# REX_9628_Extern_Kernel_8.net
KiCad netlist of a schematic drawn in Altium Designer
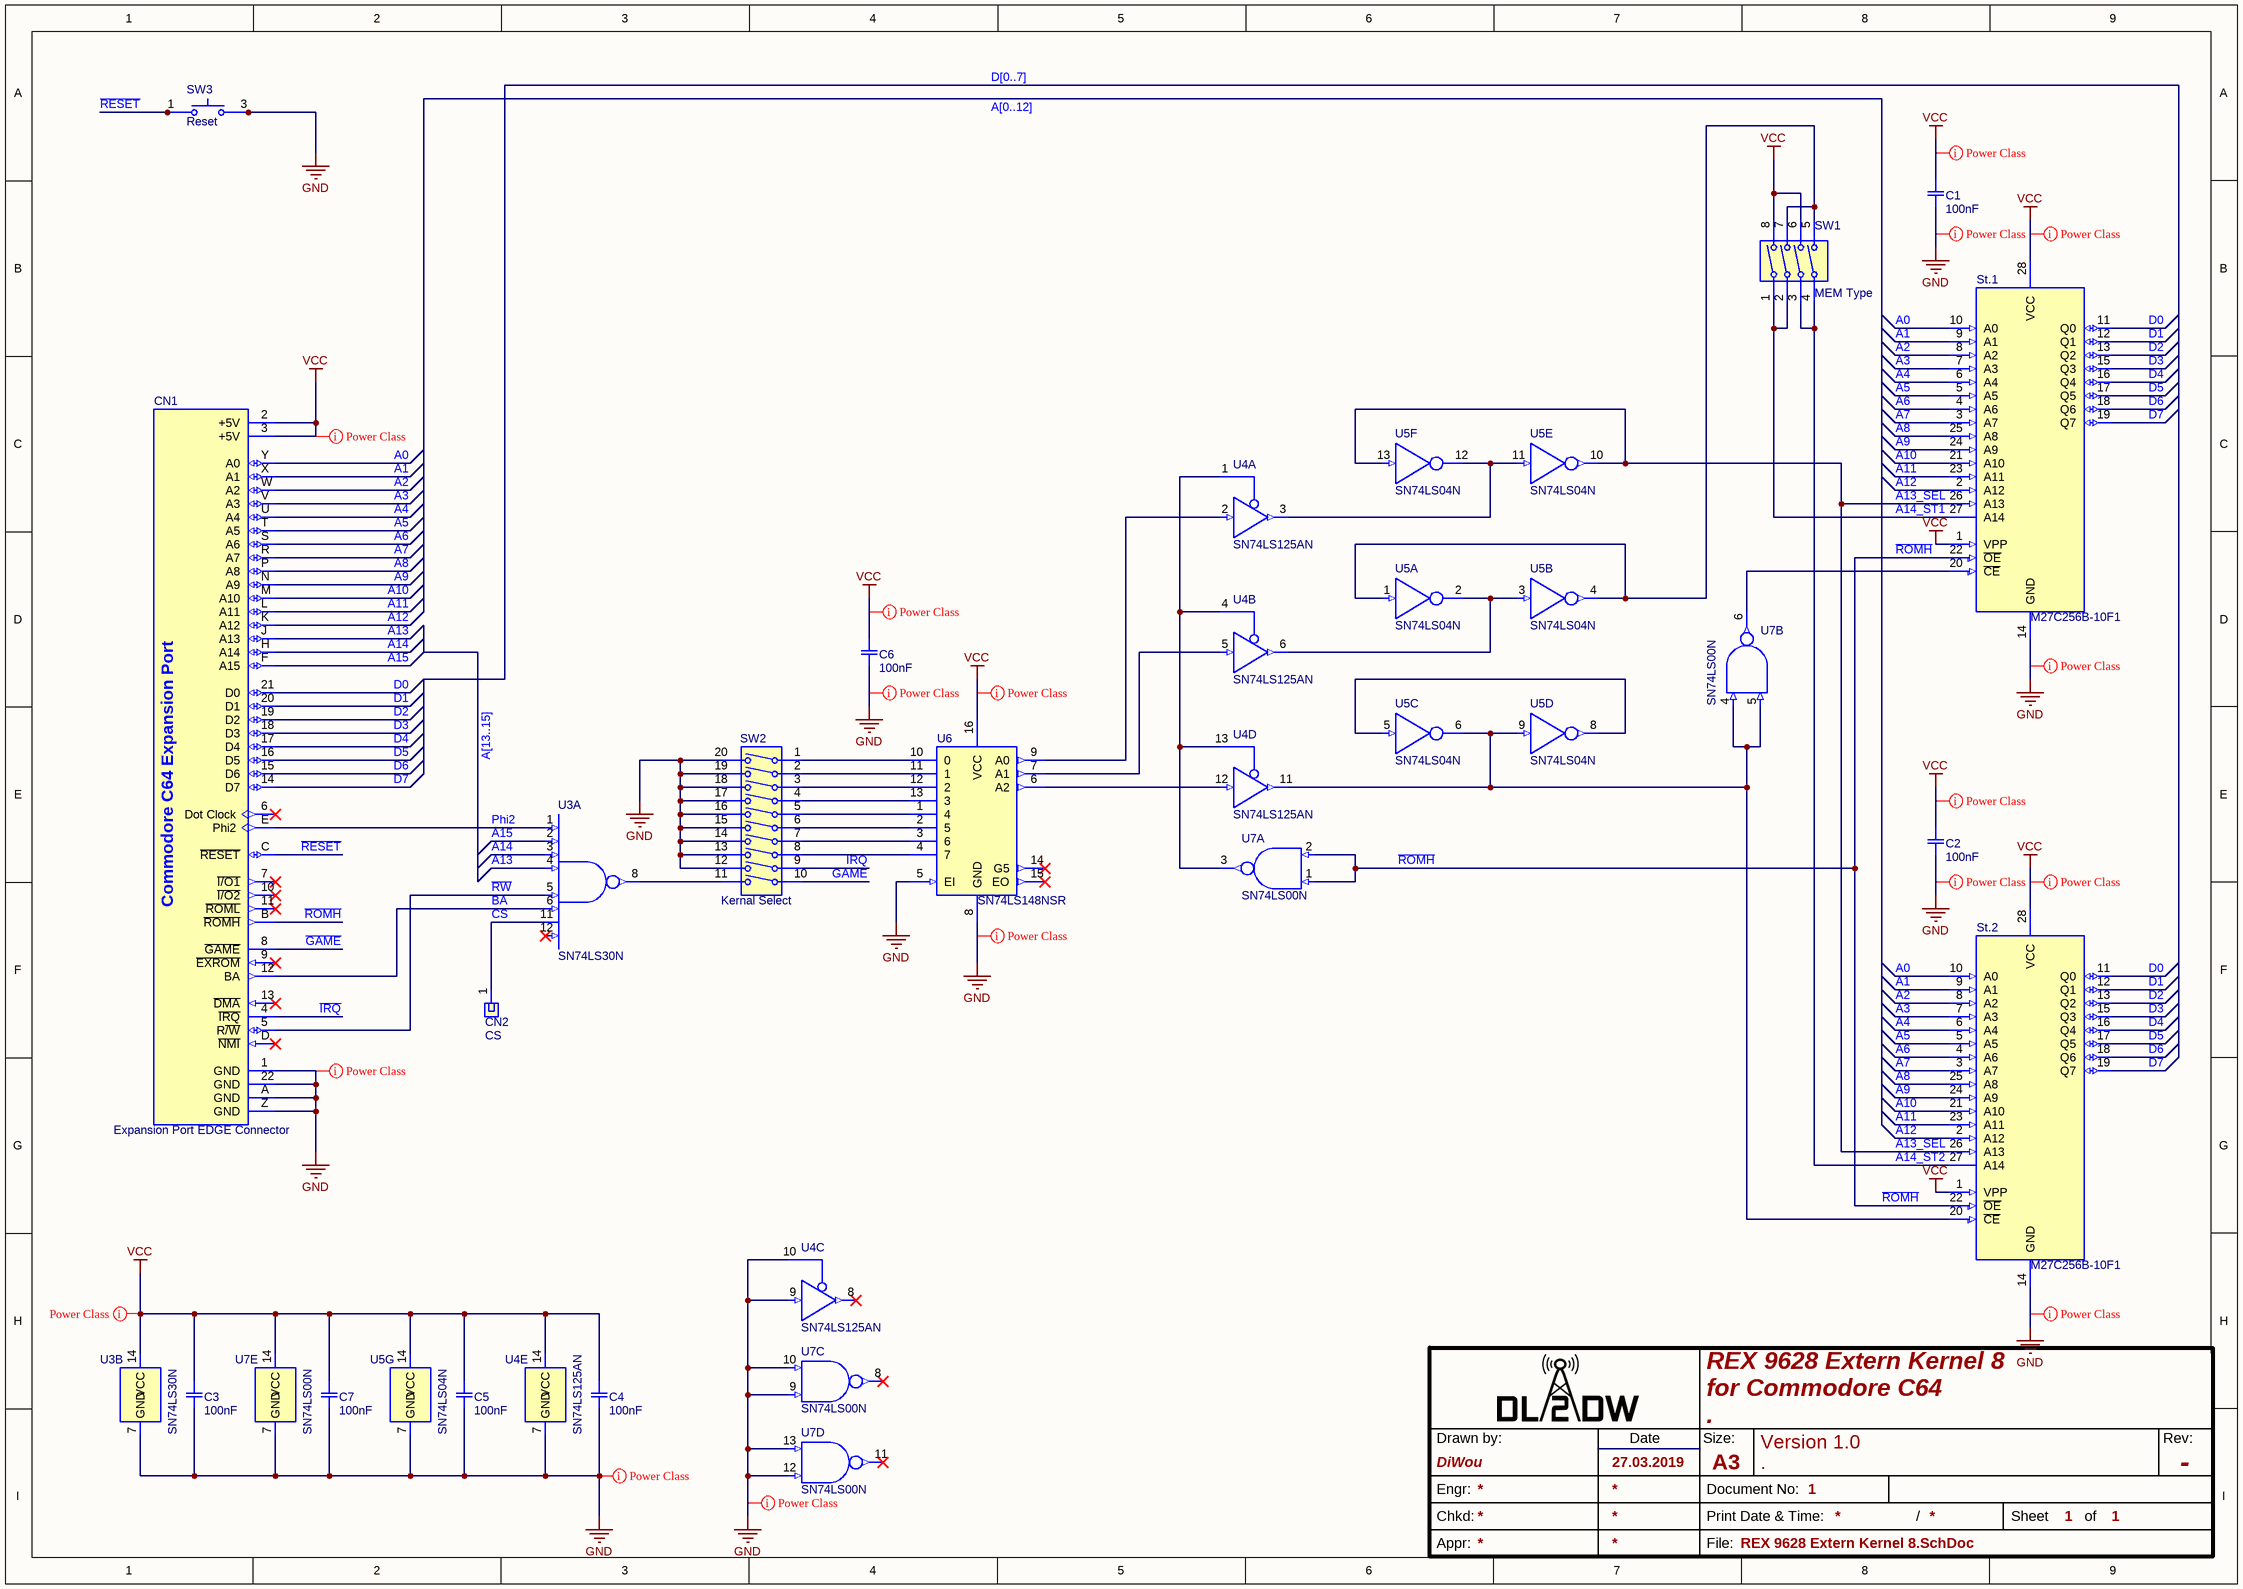
[diagram p0: REX 9628 Extern Kernel 8.SchDoc]

(export (version "E")
  (design (tool "Eeschema 10.0.6"))
  (components
    (comp (ref "C1")
      (value "100nF")
      (footprint "CAP Disc 100nF P2.54mm D5.5mm T3mm")
      (description "Ceramic Disc Capacitors 100nF -20%~+80% 50V Through Hole,P=2.54mm RoHS")
      (libsource (lib "PCB-Tech Cloud") (part "Capacitor"))
    )
    (comp (ref "C2")
      (value "100nF")
      (footprint "CAP Disc 100nF P2.54mm D5.5mm T3mm")
      (description "Ceramic Disc Capacitors 100nF -20%~+80% 50V Through Hole,P=2.54mm RoHS")
      (libsource (lib "PCB-Tech Cloud") (part "Capacitor"))
    )
    (comp (ref "C3")
      (value "100nF")
      (footprint "CAP Disc 100nF P2.54mm D5.5mm T3mm")
      (description "Ceramic Disc Capacitors 100nF -20%~+80% 50V Through Hole,P=2.54mm RoHS")
      (libsource (lib "PCB-Tech Cloud") (part "Capacitor"))
    )
    (comp (ref "C4")
      (value "100nF")
      (footprint "CAP Disc 100nF P2.54mm D5.5mm T3mm")
      (description "Ceramic Disc Capacitors 100nF -20%~+80% 50V Through Hole,P=2.54mm RoHS")
      (libsource (lib "PCB-Tech Cloud") (part "Capacitor"))
    )
    (comp (ref "C5")
      (value "100nF")
      (footprint "CAP Disc 100nF P2.54mm D5.5mm T3mm")
      (description "Ceramic Disc Capacitors 100nF -20%~+80% 50V Through Hole,P=2.54mm RoHS")
      (libsource (lib "PCB-Tech Cloud") (part "Capacitor"))
    )
    (comp (ref "C6")
      (value "100nF")
      (footprint "CAP Disc 100nF P2.54mm D5.5mm T3mm")
      (description "Ceramic Disc Capacitors 100nF -20%~+80% 50V Through Hole,P=2.54mm RoHS")
      (libsource (lib "PCB-Tech Cloud") (part "Capacitor"))
    )
    (comp (ref "C7")
      (value "100nF")
      (footprint "CAP Disc 100nF P2.54mm D5.5mm T3mm")
      (description "Ceramic Disc Capacitors 100nF -20%~+80% 50V Through Hole,P=2.54mm RoHS")
      (libsource (lib "PCB-Tech Cloud") (part "Capacitor"))
    )
    (comp (ref "CN1")
      (value "Expansion Port EDGE Connector")
      (footprint "C64 Expansion Port EDGE Connector")
      (description "Expansion Port EDGE Connector for Interface Cards")
      (libsource (lib "PCB-Tech Cloud") (part "C64 Expansion Port"))
    )
    (comp (ref "CN2")
      (value "CS")
      (footprint "Pin Header 01x01 2.54mm Horizontal Male")
      (description "CONN HEADER .100 SNGL STR 1POS")
      (libsource (lib "PCB-Tech Cloud") (part "CONN 01x01"))
    )
    (comp (ref "St.1")
      (value "M27C256B-10F1")
      (footprint "DIP-28 W15.24mm EPROM with Socket")
      (description "IC EPROM 256K PARALLEL 28CDIP")
      (libsource (lib "PCB-Tech Cloud") (part "28PIN 32kx8 EPROM 27X256"))
    )
    (comp (ref "St.2")
      (value "M27C256B-10F1")
      (footprint "DIP-28 W15.24mm EPROM with Socket")
      (description "IC EPROM 256K PARALLEL 28CDIP")
      (libsource (lib "PCB-Tech Cloud") (part "28PIN 32kx8 EPROM 27X256"))
    )
    (comp (ref "SW1")
      (value "MEM Type")
      (footprint "DIP Switch x04")
      (description "SWITCH SLIDE DIP SPST 25MA 24V")
      (libsource (lib "PCB-Tech Cloud") (part "DIP Switch x4"))
    )
    (comp (ref "SW2")
      (value "Kernal Select")
      (footprint "DIP Switch x10")
      (description "SWITCH SLIDE DIP SPST 25MA 24V")
      (libsource (lib "PCB-Tech Cloud") (part "DIP Switch x10"))
    )
    (comp (ref "SW3")
      (value "Reset")
      (footprint "Push Button 12x12mm H8.50mm THT")
      (description "Black Button Tactile Switch, NO 50 mA 5mm Through Hole")
      (libsource (lib "PCB-Tech Cloud") (part "Switch Push 4-Pin"))
    )
    (comp (ref "U3")
      (value "SN74LS30N")
      (footprint "SN74LS30N with Socket")
      (description "IC GATE NAND 1CH 8-INP 14DIP")
      (libsource (lib "PCB-Tech Cloud") (part "74xx30"))
    )
    (comp (ref "U4")
      (value "SN74LS125AN")
      (footprint "SN74LS125AN with Socket")
      (description "IC BUS BUFF TRI-ST QD 14DIP")
      (libsource (lib "PCB-Tech Cloud") (part "74xx125"))
    )
    (comp (ref "U5")
      (value "SN74LS04N")
      (footprint "SN74LS04N with Socket")
      (description "IC HEX INVERTER 14-DIP")
      (libsource (lib "PCB-Tech Cloud") (part "74xx04"))
    )
    (comp (ref "U6")
      (value "SN74LS148NSR")
      (footprint "SN74LS148N with Socket")
      (description "IC PRIORITY ENCODER 8-3L 16SO")
      (libsource (lib "PCB-Tech Cloud") (part "74xx148"))
    )
    (comp (ref "U7")
      (value "SN74LS00N")
      (footprint "SN74LS00N")
      (description "IC, 74LS, 74LS00, DIP14, 5.25V")
      (libsource (lib "") (part "74xx00_1"))
    )
  )
  (nets
    (net (code "1") (name "/A0") (class "Default")
      (node (ref "CN1") (pin "Y") (pinfunction "A0_Y") (pintype "bidirectional"))
      (node (ref "St.1") (pin "10") (pinfunction "A0_10") (pintype "input"))
      (node (ref "St.2") (pin "10") (pinfunction "A0_10") (pintype "input"))
    )
    (net (code "2") (name "/A1") (class "Default")
      (node (ref "CN1") (pin "X") (pinfunction "A1_X") (pintype "bidirectional"))
      (node (ref "St.1") (pin "9") (pinfunction "A1_9") (pintype "input"))
      (node (ref "St.2") (pin "9") (pinfunction "A1_9") (pintype "input"))
    )
    (net (code "3") (name "/A2") (class "Default")
      (node (ref "CN1") (pin "W") (pinfunction "A2_W") (pintype "bidirectional"))
      (node (ref "St.1") (pin "8") (pinfunction "A2_8") (pintype "input"))
      (node (ref "St.2") (pin "8") (pinfunction "A2_8") (pintype "input"))
    )
    (net (code "4") (name "/A3") (class "Default")
      (node (ref "CN1") (pin "V") (pinfunction "A3_V") (pintype "bidirectional"))
      (node (ref "St.1") (pin "7") (pinfunction "A3_7") (pintype "input"))
      (node (ref "St.2") (pin "7") (pinfunction "A3_7") (pintype "input"))
    )
    (net (code "5") (name "/A4") (class "Default")
      (node (ref "CN1") (pin "U") (pinfunction "A4_U") (pintype "bidirectional"))
      (node (ref "St.1") (pin "6") (pinfunction "A4_6") (pintype "input"))
      (node (ref "St.2") (pin "6") (pinfunction "A4_6") (pintype "input"))
    )
    (net (code "6") (name "/A5") (class "Default")
      (node (ref "CN1") (pin "T") (pinfunction "A5_T") (pintype "bidirectional"))
      (node (ref "St.1") (pin "5") (pinfunction "A5_5") (pintype "input"))
      (node (ref "St.2") (pin "5") (pinfunction "A5_5") (pintype "input"))
    )
    (net (code "7") (name "/A6") (class "Default")
      (node (ref "CN1") (pin "S") (pinfunction "A6_S") (pintype "bidirectional"))
      (node (ref "St.1") (pin "4") (pinfunction "A6_4") (pintype "input"))
      (node (ref "St.2") (pin "4") (pinfunction "A6_4") (pintype "input"))
    )
    (net (code "8") (name "/A7") (class "Default")
      (node (ref "CN1") (pin "R") (pinfunction "A7_R") (pintype "bidirectional"))
      (node (ref "St.1") (pin "3") (pinfunction "A7_3") (pintype "input"))
      (node (ref "St.2") (pin "3") (pinfunction "A7_3") (pintype "input"))
    )
    (net (code "9") (name "/A8") (class "Default")
      (node (ref "CN1") (pin "P") (pinfunction "A8_P") (pintype "bidirectional"))
      (node (ref "St.1") (pin "25") (pinfunction "A8_25") (pintype "input"))
      (node (ref "St.2") (pin "25") (pinfunction "A8_25") (pintype "input"))
    )
    (net (code "10") (name "/A9") (class "Default")
      (node (ref "CN1") (pin "N") (pinfunction "A9_N") (pintype "bidirectional"))
      (node (ref "St.1") (pin "24") (pinfunction "A9_24") (pintype "input"))
      (node (ref "St.2") (pin "24") (pinfunction "A9_24") (pintype "input"))
    )
    (net (code "11") (name "/A10") (class "Default")
      (node (ref "CN1") (pin "M") (pinfunction "A10_M") (pintype "bidirectional"))
      (node (ref "St.1") (pin "21") (pinfunction "A10_21") (pintype "input"))
      (node (ref "St.2") (pin "21") (pinfunction "A10_21") (pintype "input"))
    )
    (net (code "12") (name "/A11") (class "Default")
      (node (ref "CN1") (pin "L") (pinfunction "A11_L") (pintype "bidirectional"))
      (node (ref "St.1") (pin "23") (pinfunction "A11_23") (pintype "input"))
      (node (ref "St.2") (pin "23") (pinfunction "A11_23") (pintype "input"))
    )
    (net (code "13") (name "/A12") (class "Default")
      (node (ref "CN1") (pin "K") (pinfunction "A12_K") (pintype "bidirectional"))
      (node (ref "St.1") (pin "2") (pinfunction "A12_2") (pintype "input"))
      (node (ref "St.2") (pin "2") (pinfunction "A12_2") (pintype "input"))
    )
    (net (code "14") (name "/A13") (class "Default")
      (node (ref "CN1") (pin "J") (pinfunction "A13_J") (pintype "bidirectional"))
      (node (ref "U3") (pin "4") (pinfunction "D_4") (pintype "input"))
    )
    (net (code "15") (name "/A13_SEL") (class "Default")
      (node (ref "St.1") (pin "26") (pinfunction "A13_26") (pintype "input"))
      (node (ref "St.2") (pin "26") (pinfunction "A13_26") (pintype "input"))
      (node (ref "U5") (pin "10") (pinfunction "5Y_10") (pintype "output"))
      (node (ref "U5") (pin "13") (pinfunction "6A_13") (pintype "input"))
    )
    (net (code "16") (name "/A14") (class "Default")
      (node (ref "CN1") (pin "H") (pinfunction "A14_H") (pintype "bidirectional"))
      (node (ref "U3") (pin "3") (pinfunction "C_3") (pintype "input"))
    )
    (net (code "17") (name "/A14_ST1") (class "Default")
      (node (ref "SW1") (pin "1") (pinfunction "1_1") (pintype "passive"))
      (node (ref "SW1") (pin "2") (pinfunction "2_2") (pintype "passive"))
      (node (ref "St.1") (pin "27") (pinfunction "A14_27") (pintype "passive"))
    )
    (net (code "18") (name "/A14_ST2") (class "Default")
      (node (ref "SW1") (pin "3") (pinfunction "3_3") (pintype "passive"))
      (node (ref "SW1") (pin "4") (pinfunction "4_4") (pintype "passive"))
      (node (ref "St.2") (pin "27") (pinfunction "A14_27") (pintype "passive"))
    )
    (net (code "19") (name "/A15") (class "Default")
      (node (ref "CN1") (pin "F") (pinfunction "A15_F") (pintype "bidirectional"))
      (node (ref "U3") (pin "2") (pinfunction "B_2") (pintype "input"))
    )
    (net (code "22") (name "/BA") (class "Default")
      (node (ref "CN1") (pin "12") (pinfunction "BA_12") (pintype "output"))
      (node (ref "U3") (pin "6") (pinfunction "F_6") (pintype "input"))
    )
    (net (code "23") (name "/CS") (class "Default")
      (node (ref "CN2") (pin "1") (pinfunction "1_1") (pintype "passive"))
      (node (ref "U3") (pin "11") (pinfunction "F_11") (pintype "input"))
    )
    (net (code "24") (name "/D0") (class "Default")
      (node (ref "CN1") (pin "21") (pinfunction "D0_21") (pintype "bidirectional"))
      (node (ref "St.1") (pin "11") (pinfunction "Q0_11") (pintype "bidirectional"))
      (node (ref "St.2") (pin "11") (pinfunction "Q0_11") (pintype "bidirectional"))
    )
    (net (code "25") (name "/D1") (class "Default")
      (node (ref "CN1") (pin "20") (pinfunction "D1_20") (pintype "bidirectional"))
      (node (ref "St.1") (pin "12") (pinfunction "Q1_12") (pintype "bidirectional"))
      (node (ref "St.2") (pin "12") (pinfunction "Q1_12") (pintype "bidirectional"))
    )
    (net (code "26") (name "/D2") (class "Default")
      (node (ref "CN1") (pin "19") (pinfunction "D2_19") (pintype "bidirectional"))
      (node (ref "St.1") (pin "13") (pinfunction "Q2_13") (pintype "bidirectional"))
      (node (ref "St.2") (pin "13") (pinfunction "Q2_13") (pintype "bidirectional"))
    )
    (net (code "27") (name "/D3") (class "Default")
      (node (ref "CN1") (pin "18") (pinfunction "D3_18") (pintype "bidirectional"))
      (node (ref "St.1") (pin "15") (pinfunction "Q3_15") (pintype "bidirectional"))
      (node (ref "St.2") (pin "15") (pinfunction "Q3_15") (pintype "bidirectional"))
    )
    (net (code "28") (name "/D4") (class "Default")
      (node (ref "CN1") (pin "17") (pinfunction "D4_17") (pintype "bidirectional"))
      (node (ref "St.1") (pin "16") (pinfunction "Q4_16") (pintype "bidirectional"))
      (node (ref "St.2") (pin "16") (pinfunction "Q4_16") (pintype "bidirectional"))
    )
    (net (code "29") (name "/D5") (class "Default")
      (node (ref "CN1") (pin "16") (pinfunction "D5_16") (pintype "bidirectional"))
      (node (ref "St.1") (pin "17") (pinfunction "Q5_17") (pintype "bidirectional"))
      (node (ref "St.2") (pin "17") (pinfunction "Q5_17") (pintype "bidirectional"))
    )
    (net (code "30") (name "/D6") (class "Default")
      (node (ref "CN1") (pin "15") (pinfunction "D6_15") (pintype "bidirectional"))
      (node (ref "St.1") (pin "18") (pinfunction "Q6_18") (pintype "bidirectional"))
      (node (ref "St.2") (pin "18") (pinfunction "Q6_18") (pintype "bidirectional"))
    )
    (net (code "31") (name "/D7") (class "Default")
      (node (ref "CN1") (pin "14") (pinfunction "D7_14") (pintype "bidirectional"))
      (node (ref "St.1") (pin "19") (pinfunction "Q7_19") (pintype "bidirectional"))
      (node (ref "St.2") (pin "19") (pinfunction "Q7_19") (pintype "bidirectional"))
    )
    (net (code "33") (name "/Phi2") (class "Default")
      (node (ref "CN1") (pin "E") (pinfunction "Phi2_E") (pintype "output"))
      (node (ref "U3") (pin "1") (pinfunction "A_1") (pintype "input"))
    )
    (net (code "34") (name "/~{GAME}") (class "Default")
      (node (ref "CN1") (pin "8") (pinfunction "~{GAME}_8") (pintype "passive"))
      (node (ref "SW2") (pin "10") (pinfunction "10_10") (pintype "passive"))
    )
    (net (code "35") (name "/~{IRQ}") (class "Default")
      (node (ref "CN1") (pin "4") (pinfunction "~{IRQ}_4") (pintype "passive"))
      (node (ref "SW2") (pin "9") (pinfunction "9_9") (pintype "passive"))
    )
    (net (code "36") (name "/~{RESET}") (class "Default")
      (node (ref "CN1") (pin "C") (pinfunction "~{RESET}_C") (pintype "bidirectional"))
      (node (ref "SW3") (pin "1") (pinfunction "1_1") (pintype "passive"))
      (node (ref "SW3") (pin "2") (pinfunction "2_2") (pintype "passive"))
    )
    (net (code "37") (name "/~{ROMH}") (class "Default")
      (node (ref "CN1") (pin "B") (pinfunction "~{ROMH}_B") (pintype "output"))
      (node (ref "St.1") (pin "22") (pinfunction "~{OE}_22") (pintype "input"))
      (node (ref "St.2") (pin "22") (pinfunction "~{OE}_22") (pintype "input"))
      (node (ref "U7") (pin "1") (pinfunction "1A_1") (pintype "input"))
      (node (ref "U7") (pin "2") (pinfunction "1B_2") (pintype "input"))
    )
    (net (code "38") (name "/~{RW}") (class "Default")
      (node (ref "CN1") (pin "5") (pinfunction "R~{/W}_5") (pintype "bidirectional"))
      (node (ref "U3") (pin "5") (pinfunction "E_5") (pintype "input"))
    )
    (net (code "39") (name "GND") (class "Default")
      (node (ref "C1") (pin "2") (pinfunction "2_2") (pintype "passive"))
      (node (ref "C2") (pin "2") (pinfunction "2_2") (pintype "passive"))
      (node (ref "C3") (pin "2") (pinfunction "2_2") (pintype "passive"))
      (node (ref "C4") (pin "2") (pinfunction "2_2") (pintype "passive"))
      (node (ref "C5") (pin "2") (pinfunction "2_2") (pintype "passive"))
      (node (ref "C6") (pin "2") (pinfunction "2_2") (pintype "passive"))
      (node (ref "C7") (pin "2") (pinfunction "2_2") (pintype "passive"))
      (node (ref "CN1") (pin "1") (pinfunction "GND_1") (pintype "power_in"))
      (node (ref "CN1") (pin "22") (pinfunction "GND_22") (pintype "power_in"))
      (node (ref "CN1") (pin "A") (pinfunction "GND_A") (pintype "power_in"))
      (node (ref "CN1") (pin "Z") (pinfunction "GND_Z") (pintype "power_in"))
      (node (ref "SW2") (pin "12") (pinfunction "12_12") (pintype "passive"))
      (node (ref "SW2") (pin "13") (pinfunction "13_13") (pintype "passive"))
      (node (ref "SW2") (pin "14") (pinfunction "14_14") (pintype "passive"))
      (node (ref "SW2") (pin "15") (pinfunction "15_15") (pintype "passive"))
      (node (ref "SW2") (pin "16") (pinfunction "16_16") (pintype "passive"))
      (node (ref "SW2") (pin "17") (pinfunction "17_17") (pintype "passive"))
      (node (ref "SW2") (pin "18") (pinfunction "18_18") (pintype "passive"))
      (node (ref "SW2") (pin "19") (pinfunction "19_19") (pintype "passive"))
      (node (ref "SW2") (pin "20") (pinfunction "20_20") (pintype "passive"))
      (node (ref "SW3") (pin "3") (pinfunction "3_3") (pintype "passive"))
      (node (ref "SW3") (pin "4") (pinfunction "4_4") (pintype "passive"))
      (node (ref "St.1") (pin "14") (pinfunction "GND_14") (pintype "passive"))
      (node (ref "St.2") (pin "14") (pinfunction "GND_14") (pintype "passive"))
      (node (ref "U3") (pin "7") (pinfunction "GND_7") (pintype "passive"))
      (node (ref "U4") (pin "10") (pinfunction "~{3G}_10") (pintype "passive"))
      (node (ref "U4") (pin "7") (pinfunction "GND_7") (pintype "passive"))
      (node (ref "U4") (pin "9") (pinfunction "3A_9") (pintype "input"))
      (node (ref "U5") (pin "7") (pinfunction "GND_7") (pintype "passive"))
      (node (ref "U6") (pin "5") (pinfunction "EI_5") (pintype "input"))
      (node (ref "U6") (pin "8") (pinfunction "GND_8") (pintype "passive"))
      (node (ref "U7") (pin "10") (pinfunction "3A_10") (pintype "input"))
      (node (ref "U7") (pin "12") (pinfunction "4B_12") (pintype "input"))
      (node (ref "U7") (pin "13") (pinfunction "4A_13") (pintype "input"))
      (node (ref "U7") (pin "7") (pinfunction "GND_7") (pintype "passive"))
      (node (ref "U7") (pin "9") (pinfunction "3B_9") (pintype "input"))
    )
    (net (code "40") (name "Net-(St.1-~{CE})") (class "Default")
      (node (ref "St.1") (pin "20") (pinfunction "~{CE}_20") (pintype "input"))
      (node (ref "U7") (pin "6") (pinfunction "2Y_6") (pintype "output"))
    )
    (net (code "41") (name "Net-(St.2-~{CE})") (class "Default")
      (node (ref "St.2") (pin "20") (pinfunction "~{CE}_20") (pintype "input"))
      (node (ref "U4") (pin "11") (pinfunction "4Y_11") (pintype "output"))
      (node (ref "U5") (pin "6") (pinfunction "3Y_6") (pintype "output"))
      (node (ref "U5") (pin "9") (pinfunction "4A_9") (pintype "input"))
      (node (ref "U7") (pin "4") (pinfunction "2A_4") (pintype "input"))
      (node (ref "U7") (pin "5") (pinfunction "2B_5") (pintype "input"))
    )
    (net (code "42") (name "Net-(U3A-1Y)") (class "Default")
      (node (ref "SW2") (pin "11") (pinfunction "11_11") (pintype "passive"))
      (node (ref "U3") (pin "8") (pinfunction "1Y_8") (pintype "output"))
    )
    (net (code "43") (name "Net-(U4A-1A)") (class "Default")
      (node (ref "U4") (pin "2") (pinfunction "1A_2") (pintype "input"))
      (node (ref "U6") (pin "9") (pinfunction "A0_9") (pintype "output"))
    )
    (net (code "44") (name "Net-(U4A-1Y)") (class "Default")
      (node (ref "U4") (pin "3") (pinfunction "1Y_3") (pintype "output"))
      (node (ref "U5") (pin "11") (pinfunction "5A_11") (pintype "input"))
      (node (ref "U5") (pin "12") (pinfunction "6Y_12") (pintype "output"))
    )
    (net (code "45") (name "Net-(U4A-~{1G})") (class "Default")
      (node (ref "U4") (pin "1") (pinfunction "~{1G}_1") (pintype "passive"))
      (node (ref "U4") (pin "13") (pinfunction "~{4G}_13") (pintype "passive"))
      (node (ref "U4") (pin "4") (pinfunction "~{2G}_4") (pintype "passive"))
      (node (ref "U7") (pin "3") (pinfunction "1Y_3") (pintype "output"))
    )
    (net (code "46") (name "Net-(U4B-2A)") (class "Default")
      (node (ref "U4") (pin "5") (pinfunction "2A_5") (pintype "input"))
      (node (ref "U6") (pin "7") (pinfunction "A1_7") (pintype "output"))
    )
    (net (code "47") (name "Net-(U4B-2Y)") (class "Default")
      (node (ref "U4") (pin "6") (pinfunction "2Y_6") (pintype "output"))
      (node (ref "U5") (pin "2") (pinfunction "1Y_2") (pintype "output"))
      (node (ref "U5") (pin "3") (pinfunction "2A_3") (pintype "input"))
    )
    (net (code "48") (name "Net-(U4D-4A)") (class "Default")
      (node (ref "U4") (pin "12") (pinfunction "4A_12") (pintype "input"))
      (node (ref "U6") (pin "6") (pinfunction "A2_6") (pintype "output"))
    )
    (net (code "49") (name "Net-(U5A-1A)") (class "Default")
      (node (ref "SW1") (pin "5") (pinfunction "5_5") (pintype "passive"))
      (node (ref "SW1") (pin "7") (pinfunction "7_7") (pintype "passive"))
      (node (ref "U5") (pin "1") (pinfunction "1A_1") (pintype "input"))
      (node (ref "U5") (pin "4") (pinfunction "2Y_4") (pintype "output"))
    )
    (net (code "50") (name "Net-(U5C-3A)") (class "Default")
      (node (ref "U5") (pin "5") (pinfunction "3A_5") (pintype "input"))
      (node (ref "U5") (pin "8") (pinfunction "4Y_8") (pintype "output"))
    )
    (net (code "51") (name "Net-(U6-0)") (class "Default")
      (node (ref "SW2") (pin "1") (pinfunction "1_1") (pintype "passive"))
      (node (ref "U6") (pin "10") (pinfunction "0_10") (pintype "passive"))
    )
    (net (code "52") (name "Net-(U6-1)") (class "Default")
      (node (ref "SW2") (pin "2") (pinfunction "2_2") (pintype "passive"))
      (node (ref "U6") (pin "11") (pinfunction "1_11") (pintype "passive"))
    )
    (net (code "53") (name "Net-(U6-2)") (class "Default")
      (node (ref "SW2") (pin "3") (pinfunction "3_3") (pintype "passive"))
      (node (ref "U6") (pin "12") (pinfunction "2_12") (pintype "passive"))
    )
    (net (code "54") (name "Net-(U6-3)") (class "Default")
      (node (ref "SW2") (pin "4") (pinfunction "4_4") (pintype "passive"))
      (node (ref "U6") (pin "13") (pinfunction "3_13") (pintype "passive"))
    )
    (net (code "55") (name "Net-(U6-4)") (class "Default")
      (node (ref "SW2") (pin "5") (pinfunction "5_5") (pintype "passive"))
      (node (ref "U6") (pin "1") (pinfunction "4_1") (pintype "passive"))
    )
    (net (code "56") (name "Net-(U6-5)") (class "Default")
      (node (ref "SW2") (pin "6") (pinfunction "6_6") (pintype "passive"))
      (node (ref "U6") (pin "2") (pinfunction "5_2") (pintype "passive"))
    )
    (net (code "57") (name "Net-(U6-6)") (class "Default")
      (node (ref "SW2") (pin "7") (pinfunction "7_7") (pintype "passive"))
      (node (ref "U6") (pin "3") (pinfunction "6_3") (pintype "passive"))
    )
    (net (code "58") (name "Net-(U6-7)") (class "Default")
      (node (ref "SW2") (pin "8") (pinfunction "8_8") (pintype "passive"))
      (node (ref "U6") (pin "4") (pinfunction "7_4") (pintype "passive"))
    )
    (net (code "59") (name "VCC") (class "Default")
      (node (ref "C1") (pin "1") (pinfunction "1_1") (pintype "passive"))
      (node (ref "C2") (pin "1") (pinfunction "1_1") (pintype "passive"))
      (node (ref "C3") (pin "1") (pinfunction "1_1") (pintype "passive"))
      (node (ref "C4") (pin "1") (pinfunction "1_1") (pintype "passive"))
      (node (ref "C5") (pin "1") (pinfunction "1_1") (pintype "passive"))
      (node (ref "C6") (pin "1") (pinfunction "1_1") (pintype "passive"))
      (node (ref "C7") (pin "1") (pinfunction "1_1") (pintype "passive"))
      (node (ref "CN1") (pin "2") (pinfunction "+5V_2") (pintype "power_in"))
      (node (ref "CN1") (pin "3") (pinfunction "+5V_3") (pintype "power_in"))
      (node (ref "SW1") (pin "6") (pinfunction "6_6") (pintype "passive"))
      (node (ref "SW1") (pin "8") (pinfunction "8_8") (pintype "passive"))
      (node (ref "St.1") (pin "1") (pinfunction "VPP_1") (pintype "input"))
      (node (ref "St.1") (pin "28") (pinfunction "VCC_28") (pintype "power_in"))
      (node (ref "St.2") (pin "1") (pinfunction "VPP_1") (pintype "input"))
      (node (ref "St.2") (pin "28") (pinfunction "VCC_28") (pintype "power_in"))
      (node (ref "U3") (pin "14") (pinfunction "VCC_14") (pintype "power_in"))
      (node (ref "U4") (pin "14") (pinfunction "VCC_14") (pintype "power_in"))
      (node (ref "U5") (pin "14") (pinfunction "VCC_14") (pintype "power_in"))
      (node (ref "U6") (pin "16") (pinfunction "VCC_16") (pintype "power_in"))
      (node (ref "U7") (pin "14") (pinfunction "VCC_14") (pintype "power_in"))
    )
    (net (code "60") (name "unconnected-(CN1-Dot_Clock-Pad6)") (class "Default")
      (node (ref "CN1") (pin "6") (pinfunction "Dot_Clock_6") (pintype "output+no_connect"))
    )
    (net (code "61") (name "unconnected-(CN1-~{DMA}-Pad13)") (class "Default")
      (node (ref "CN1") (pin "13") (pinfunction "~{DMA}_13") (pintype "input+no_connect"))
    )
    (net (code "62") (name "unconnected-(CN1-~{EXROM}-Pad9)") (class "Default")
      (node (ref "CN1") (pin "9") (pinfunction "~{EXROM}_9") (pintype "input+no_connect"))
    )
    (net (code "63") (name "unconnected-(CN1-~{I{slash}O1}-Pad7)") (class "Default")
      (node (ref "CN1") (pin "7") (pinfunction "~{I/O1}_7") (pintype "output+no_connect"))
    )
    (net (code "64") (name "unconnected-(CN1-~{I{slash}O2}-Pad10)") (class "Default")
      (node (ref "CN1") (pin "10") (pinfunction "~{I/O2}_10") (pintype "output+no_connect"))
    )
    (net (code "65") (name "unconnected-(CN1-~{NMI}-PadD)") (class "Default")
      (node (ref "CN1") (pin "D") (pinfunction "~{NMI}_D") (pintype "input+no_connect"))
    )
    (net (code "66") (name "unconnected-(CN1-~{ROML}-Pad11)") (class "Default")
      (node (ref "CN1") (pin "11") (pinfunction "~{ROML}_11") (pintype "output+no_connect"))
    )
    (net (code "67") (name "unconnected-(U3A-H-Pad12)") (class "Default")
      (node (ref "U3") (pin "12") (pinfunction "H_12") (pintype "input+no_connect"))
    )
    (net (code "68") (name "unconnected-(U3A-N{slash}C-Pad9)") (class "Default")
      (node (ref "U3") (pin "9") (pinfunction "N/C_9") (pintype "passive"))
    )
    (net (code "69") (name "unconnected-(U3A-N{slash}C-Pad10)") (class "Default")
      (node (ref "U3") (pin "10") (pinfunction "N/C_10") (pintype "passive"))
    )
    (net (code "70") (name "unconnected-(U3A-N{slash}C-Pad13)") (class "Default")
      (node (ref "U3") (pin "13") (pinfunction "N/C_13") (pintype "passive"))
    )
    (net (code "71") (name "unconnected-(U4C-3Y-Pad8)") (class "Default")
      (node (ref "U4") (pin "8") (pinfunction "3Y_8") (pintype "output+no_connect"))
    )
    (net (code "72") (name "unconnected-(U6-EO-Pad15)") (class "Default")
      (node (ref "U6") (pin "15") (pinfunction "EO_15") (pintype "output+no_connect"))
    )
    (net (code "73") (name "unconnected-(U6-G5-Pad14)") (class "Default")
      (node (ref "U6") (pin "14") (pinfunction "G5_14") (pintype "output+no_connect"))
    )
    (net (code "74") (name "unconnected-(U7C-3Y-Pad8)") (class "Default")
      (node (ref "U7") (pin "8") (pinfunction "3Y_8") (pintype "output+no_connect"))
    )
    (net (code "75") (name "unconnected-(U7D-4Y-Pad11)") (class "Default")
      (node (ref "U7") (pin "11") (pinfunction "4Y_11") (pintype "output+no_connect"))
    )
  )
)
